# brake_light.net
KiCad netlist of a schematic drawn in EAGLE
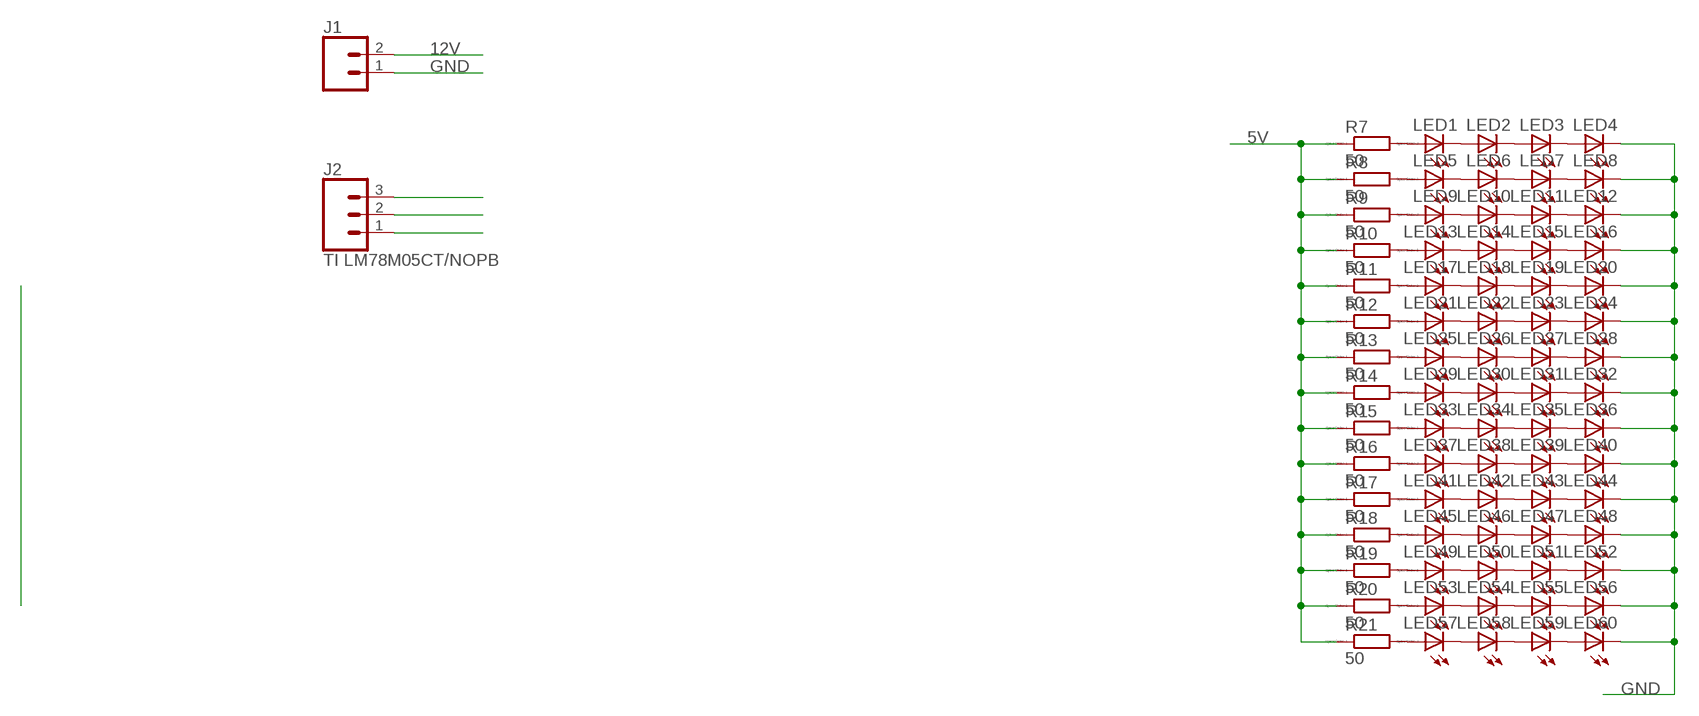
[diagram p0: schematic, sheet 1]

(export (version "E")
  (design (tool "Eeschema 10.0.6"))
  (components
    (comp (ref "J1")
      (value "CONN_02")
      (footprint "eagle-import:1X02")
      (libsource (lib "eagle-import") (part "CONN_02"))
    )
    (comp (ref "J2")
      (value "TI LM78M05CT/NOPB")
      (footprint "eagle-import:1X03")
      (libsource (lib "eagle-import") (part "CONN_03"))
    )
    (comp (ref "LED1")
      (value "LED5MM")
      (footprint "eagle-import:LED5MM")
      (libsource (lib "eagle-import") (part "LED5MM"))
    )
    (comp (ref "LED2")
      (value "LED5MM")
      (footprint "eagle-import:LED5MM")
      (libsource (lib "eagle-import") (part "LED5MM"))
    )
    (comp (ref "LED3")
      (value "LED5MM")
      (footprint "eagle-import:LED5MM")
      (libsource (lib "eagle-import") (part "LED5MM"))
    )
    (comp (ref "LED4")
      (value "LED5MM")
      (footprint "eagle-import:LED5MM")
      (libsource (lib "eagle-import") (part "LED5MM"))
    )
    (comp (ref "LED5")
      (value "LED5MM")
      (footprint "eagle-import:LED5MM")
      (libsource (lib "eagle-import") (part "LED5MM"))
    )
    (comp (ref "LED6")
      (value "LED5MM")
      (footprint "eagle-import:LED5MM")
      (libsource (lib "eagle-import") (part "LED5MM"))
    )
    (comp (ref "LED7")
      (value "LED5MM")
      (footprint "eagle-import:LED5MM")
      (libsource (lib "eagle-import") (part "LED5MM"))
    )
    (comp (ref "LED8")
      (value "LED5MM")
      (footprint "eagle-import:LED5MM")
      (libsource (lib "eagle-import") (part "LED5MM"))
    )
    (comp (ref "LED9")
      (value "LED5MM")
      (footprint "eagle-import:LED5MM")
      (libsource (lib "eagle-import") (part "LED5MM"))
    )
    (comp (ref "LED10")
      (value "LED5MM")
      (footprint "eagle-import:LED5MM")
      (libsource (lib "eagle-import") (part "LED5MM"))
    )
    (comp (ref "LED11")
      (value "LED5MM")
      (footprint "eagle-import:LED5MM")
      (libsource (lib "eagle-import") (part "LED5MM"))
    )
    (comp (ref "LED12")
      (value "LED5MM")
      (footprint "eagle-import:LED5MM")
      (libsource (lib "eagle-import") (part "LED5MM"))
    )
    (comp (ref "LED13")
      (value "LED5MM")
      (footprint "eagle-import:LED5MM")
      (libsource (lib "eagle-import") (part "LED5MM"))
    )
    (comp (ref "LED14")
      (value "LED5MM")
      (footprint "eagle-import:LED5MM")
      (libsource (lib "eagle-import") (part "LED5MM"))
    )
    (comp (ref "LED15")
      (value "LED5MM")
      (footprint "eagle-import:LED5MM")
      (libsource (lib "eagle-import") (part "LED5MM"))
    )
    (comp (ref "LED16")
      (value "LED5MM")
      (footprint "eagle-import:LED5MM")
      (libsource (lib "eagle-import") (part "LED5MM"))
    )
    (comp (ref "LED17")
      (value "LED5MM")
      (footprint "eagle-import:LED5MM")
      (libsource (lib "eagle-import") (part "LED5MM"))
    )
    (comp (ref "LED18")
      (value "LED5MM")
      (footprint "eagle-import:LED5MM")
      (libsource (lib "eagle-import") (part "LED5MM"))
    )
    (comp (ref "LED19")
      (value "LED5MM")
      (footprint "eagle-import:LED5MM")
      (libsource (lib "eagle-import") (part "LED5MM"))
    )
    (comp (ref "LED20")
      (value "LED5MM")
      (footprint "eagle-import:LED5MM")
      (libsource (lib "eagle-import") (part "LED5MM"))
    )
    (comp (ref "LED21")
      (value "LED5MM")
      (footprint "eagle-import:LED5MM")
      (libsource (lib "eagle-import") (part "LED5MM"))
    )
    (comp (ref "LED22")
      (value "LED5MM")
      (footprint "eagle-import:LED5MM")
      (libsource (lib "eagle-import") (part "LED5MM"))
    )
    (comp (ref "LED23")
      (value "LED5MM")
      (footprint "eagle-import:LED5MM")
      (libsource (lib "eagle-import") (part "LED5MM"))
    )
    (comp (ref "LED24")
      (value "LED5MM")
      (footprint "eagle-import:LED5MM")
      (libsource (lib "eagle-import") (part "LED5MM"))
    )
    (comp (ref "LED25")
      (value "LED5MM")
      (footprint "eagle-import:LED5MM")
      (libsource (lib "eagle-import") (part "LED5MM"))
    )
    (comp (ref "LED26")
      (value "LED5MM")
      (footprint "eagle-import:LED5MM")
      (libsource (lib "eagle-import") (part "LED5MM"))
    )
    (comp (ref "LED27")
      (value "LED5MM")
      (footprint "eagle-import:LED5MM")
      (libsource (lib "eagle-import") (part "LED5MM"))
    )
    (comp (ref "LED28")
      (value "LED5MM")
      (footprint "eagle-import:LED5MM")
      (libsource (lib "eagle-import") (part "LED5MM"))
    )
    (comp (ref "LED29")
      (value "LED5MM")
      (footprint "eagle-import:LED5MM")
      (libsource (lib "eagle-import") (part "LED5MM"))
    )
    (comp (ref "LED30")
      (value "LED5MM")
      (footprint "eagle-import:LED5MM")
      (libsource (lib "eagle-import") (part "LED5MM"))
    )
    (comp (ref "LED31")
      (value "LED5MM")
      (footprint "eagle-import:LED5MM")
      (libsource (lib "eagle-import") (part "LED5MM"))
    )
    (comp (ref "LED32")
      (value "LED5MM")
      (footprint "eagle-import:LED5MM")
      (libsource (lib "eagle-import") (part "LED5MM"))
    )
    (comp (ref "LED33")
      (value "LED5MM")
      (footprint "eagle-import:LED5MM")
      (libsource (lib "eagle-import") (part "LED5MM"))
    )
    (comp (ref "LED34")
      (value "LED5MM")
      (footprint "eagle-import:LED5MM")
      (libsource (lib "eagle-import") (part "LED5MM"))
    )
    (comp (ref "LED35")
      (value "LED5MM")
      (footprint "eagle-import:LED5MM")
      (libsource (lib "eagle-import") (part "LED5MM"))
    )
    (comp (ref "LED36")
      (value "LED5MM")
      (footprint "eagle-import:LED5MM")
      (libsource (lib "eagle-import") (part "LED5MM"))
    )
    (comp (ref "LED37")
      (value "LED5MM")
      (footprint "eagle-import:LED5MM")
      (libsource (lib "eagle-import") (part "LED5MM"))
    )
    (comp (ref "LED38")
      (value "LED5MM")
      (footprint "eagle-import:LED5MM")
      (libsource (lib "eagle-import") (part "LED5MM"))
    )
    (comp (ref "LED39")
      (value "LED5MM")
      (footprint "eagle-import:LED5MM")
      (libsource (lib "eagle-import") (part "LED5MM"))
    )
    (comp (ref "LED40")
      (value "LED5MM")
      (footprint "eagle-import:LED5MM")
      (libsource (lib "eagle-import") (part "LED5MM"))
    )
    (comp (ref "LED41")
      (value "LED5MM")
      (footprint "eagle-import:LED5MM")
      (libsource (lib "eagle-import") (part "LED5MM"))
    )
    (comp (ref "LED42")
      (value "LED5MM")
      (footprint "eagle-import:LED5MM")
      (libsource (lib "eagle-import") (part "LED5MM"))
    )
    (comp (ref "LED43")
      (value "LED5MM")
      (footprint "eagle-import:LED5MM")
      (libsource (lib "eagle-import") (part "LED5MM"))
    )
    (comp (ref "LED44")
      (value "LED5MM")
      (footprint "eagle-import:LED5MM")
      (libsource (lib "eagle-import") (part "LED5MM"))
    )
    (comp (ref "LED45")
      (value "LED5MM")
      (footprint "eagle-import:LED5MM")
      (libsource (lib "eagle-import") (part "LED5MM"))
    )
    (comp (ref "LED46")
      (value "LED5MM")
      (footprint "eagle-import:LED5MM")
      (libsource (lib "eagle-import") (part "LED5MM"))
    )
    (comp (ref "LED47")
      (value "LED5MM")
      (footprint "eagle-import:LED5MM")
      (libsource (lib "eagle-import") (part "LED5MM"))
    )
    (comp (ref "LED48")
      (value "LED5MM")
      (footprint "eagle-import:LED5MM")
      (libsource (lib "eagle-import") (part "LED5MM"))
    )
    (comp (ref "LED49")
      (value "LED5MM")
      (footprint "eagle-import:LED5MM")
      (libsource (lib "eagle-import") (part "LED5MM"))
    )
    (comp (ref "LED50")
      (value "LED5MM")
      (footprint "eagle-import:LED5MM")
      (libsource (lib "eagle-import") (part "LED5MM"))
    )
    (comp (ref "LED51")
      (value "LED5MM")
      (footprint "eagle-import:LED5MM")
      (libsource (lib "eagle-import") (part "LED5MM"))
    )
    (comp (ref "LED52")
      (value "LED5MM")
      (footprint "eagle-import:LED5MM")
      (libsource (lib "eagle-import") (part "LED5MM"))
    )
    (comp (ref "LED53")
      (value "LED5MM")
      (footprint "eagle-import:LED5MM")
      (libsource (lib "eagle-import") (part "LED5MM"))
    )
    (comp (ref "LED54")
      (value "LED5MM")
      (footprint "eagle-import:LED5MM")
      (libsource (lib "eagle-import") (part "LED5MM"))
    )
    (comp (ref "LED55")
      (value "LED5MM")
      (footprint "eagle-import:LED5MM")
      (libsource (lib "eagle-import") (part "LED5MM"))
    )
    (comp (ref "LED56")
      (value "LED5MM")
      (footprint "eagle-import:LED5MM")
      (libsource (lib "eagle-import") (part "LED5MM"))
    )
    (comp (ref "LED57")
      (value "LED5MM")
      (footprint "eagle-import:LED5MM")
      (libsource (lib "eagle-import") (part "LED5MM"))
    )
    (comp (ref "LED58")
      (value "LED5MM")
      (footprint "eagle-import:LED5MM")
      (libsource (lib "eagle-import") (part "LED5MM"))
    )
    (comp (ref "LED59")
      (value "LED5MM")
      (footprint "eagle-import:LED5MM")
      (libsource (lib "eagle-import") (part "LED5MM"))
    )
    (comp (ref "LED60")
      (value "LED5MM")
      (footprint "eagle-import:LED5MM")
      (libsource (lib "eagle-import") (part "LED5MM"))
    )
    (comp (ref "R7")
      (value "50")
      (footprint "eagle-import:R1206")
      (libsource (lib "eagle-import") (part "RR1206"))
    )
    (comp (ref "R8")
      (value "50")
      (footprint "eagle-import:R1206")
      (libsource (lib "eagle-import") (part "RR1206"))
    )
    (comp (ref "R9")
      (value "50")
      (footprint "eagle-import:R1206")
      (libsource (lib "eagle-import") (part "RR1206"))
    )
    (comp (ref "R10")
      (value "50")
      (footprint "eagle-import:R1206")
      (libsource (lib "eagle-import") (part "RR1206"))
    )
    (comp (ref "R11")
      (value "50")
      (footprint "eagle-import:R1206")
      (libsource (lib "eagle-import") (part "RR1206"))
    )
    (comp (ref "R12")
      (value "50")
      (footprint "eagle-import:R1206")
      (libsource (lib "eagle-import") (part "RR1206"))
    )
    (comp (ref "R13")
      (value "50")
      (footprint "eagle-import:R1206")
      (libsource (lib "eagle-import") (part "RR1206"))
    )
    (comp (ref "R14")
      (value "50")
      (footprint "eagle-import:R1206")
      (libsource (lib "eagle-import") (part "RR1206"))
    )
    (comp (ref "R15")
      (value "50")
      (footprint "eagle-import:R1206")
      (libsource (lib "eagle-import") (part "RR1206"))
    )
    (comp (ref "R16")
      (value "50")
      (footprint "eagle-import:R1206")
      (libsource (lib "eagle-import") (part "RR1206"))
    )
    (comp (ref "R17")
      (value "50")
      (footprint "eagle-import:R1206")
      (libsource (lib "eagle-import") (part "RR1206"))
    )
    (comp (ref "R18")
      (value "50")
      (footprint "eagle-import:R1206")
      (libsource (lib "eagle-import") (part "RR1206"))
    )
    (comp (ref "R19")
      (value "50")
      (footprint "eagle-import:R1206")
      (libsource (lib "eagle-import") (part "RR1206"))
    )
    (comp (ref "R20")
      (value "50")
      (footprint "eagle-import:R1206")
      (libsource (lib "eagle-import") (part "RR1206"))
    )
    (comp (ref "R21")
      (value "50")
      (footprint "eagle-import:R1206")
      (libsource (lib "eagle-import") (part "RR1206"))
    )
  )
  (nets
    (net (code "1") (name "/5V") (class "Default")
      (node (ref "J2") (pin "3") (pinfunction "3_3") (pintype "passive"))
      (node (ref "R10") (pin "1") (pinfunction "1_1") (pintype "passive"))
      (node (ref "R11") (pin "1") (pinfunction "1_1") (pintype "passive"))
      (node (ref "R12") (pin "1") (pinfunction "1_1") (pintype "passive"))
      (node (ref "R13") (pin "1") (pinfunction "1_1") (pintype "passive"))
      (node (ref "R14") (pin "1") (pinfunction "1_1") (pintype "passive"))
      (node (ref "R15") (pin "1") (pinfunction "1_1") (pintype "passive"))
      (node (ref "R16") (pin "1") (pinfunction "1_1") (pintype "passive"))
      (node (ref "R17") (pin "1") (pinfunction "1_1") (pintype "passive"))
      (node (ref "R18") (pin "1") (pinfunction "1_1") (pintype "passive"))
      (node (ref "R19") (pin "1") (pinfunction "1_1") (pintype "passive"))
      (node (ref "R20") (pin "1") (pinfunction "1_1") (pintype "passive"))
      (node (ref "R21") (pin "1") (pinfunction "1_1") (pintype "passive"))
      (node (ref "R7") (pin "1") (pinfunction "1_1") (pintype "passive"))
      (node (ref "R8") (pin "1") (pinfunction "1_1") (pintype "passive"))
      (node (ref "R9") (pin "1") (pinfunction "1_1") (pintype "passive"))
    )
    (net (code "2") (name "/12V") (class "Default")
      (node (ref "J1") (pin "2") (pinfunction "2_2") (pintype "passive"))
      (node (ref "J2") (pin "1") (pinfunction "1_1") (pintype "passive"))
    )
    (net (code "3") (name "/GND") (class "Default")
      (node (ref "J1") (pin "1") (pinfunction "1_1") (pintype "passive"))
      (node (ref "J2") (pin "2") (pinfunction "2_2") (pintype "passive"))
      (node (ref "LED12") (pin "K") (pinfunction "C_K") (pintype "passive"))
      (node (ref "LED16") (pin "K") (pinfunction "C_K") (pintype "passive"))
      (node (ref "LED20") (pin "K") (pinfunction "C_K") (pintype "passive"))
      (node (ref "LED24") (pin "K") (pinfunction "C_K") (pintype "passive"))
      (node (ref "LED28") (pin "K") (pinfunction "C_K") (pintype "passive"))
      (node (ref "LED32") (pin "K") (pinfunction "C_K") (pintype "passive"))
      (node (ref "LED36") (pin "K") (pinfunction "C_K") (pintype "passive"))
      (node (ref "LED4") (pin "K") (pinfunction "C_K") (pintype "passive"))
      (node (ref "LED40") (pin "K") (pinfunction "C_K") (pintype "passive"))
      (node (ref "LED44") (pin "K") (pinfunction "C_K") (pintype "passive"))
      (node (ref "LED48") (pin "K") (pinfunction "C_K") (pintype "passive"))
      (node (ref "LED52") (pin "K") (pinfunction "C_K") (pintype "passive"))
      (node (ref "LED56") (pin "K") (pinfunction "C_K") (pintype "passive"))
      (node (ref "LED60") (pin "K") (pinfunction "C_K") (pintype "passive"))
      (node (ref "LED8") (pin "K") (pinfunction "C_K") (pintype "passive"))
    )
    (net (code "4") (name "Net-(LED1-C)") (class "Default")
      (node (ref "LED1") (pin "K") (pinfunction "C_K") (pintype "passive"))
      (node (ref "LED2") (pin "A") (pinfunction "A_A") (pintype "passive"))
    )
    (net (code "5") (name "Net-(LED1-PadA)") (class "Default")
      (node (ref "LED1") (pin "A") (pinfunction "A_A") (pintype "passive"))
      (node (ref "R7") (pin "2") (pinfunction "2_2") (pintype "passive"))
    )
    (net (code "6") (name "Net-(LED2-C)") (class "Default")
      (node (ref "LED2") (pin "K") (pinfunction "C_K") (pintype "passive"))
      (node (ref "LED3") (pin "A") (pinfunction "A_A") (pintype "passive"))
    )
    (net (code "7") (name "Net-(LED3-C)") (class "Default")
      (node (ref "LED3") (pin "K") (pinfunction "C_K") (pintype "passive"))
      (node (ref "LED4") (pin "A") (pinfunction "A_A") (pintype "passive"))
    )
    (net (code "8") (name "Net-(LED5-C)") (class "Default")
      (node (ref "LED5") (pin "K") (pinfunction "C_K") (pintype "passive"))
      (node (ref "LED6") (pin "A") (pinfunction "A_A") (pintype "passive"))
    )
    (net (code "9") (name "Net-(LED5-PadA)") (class "Default")
      (node (ref "LED5") (pin "A") (pinfunction "A_A") (pintype "passive"))
      (node (ref "R8") (pin "2") (pinfunction "2_2") (pintype "passive"))
    )
    (net (code "10") (name "Net-(LED6-C)") (class "Default")
      (node (ref "LED6") (pin "K") (pinfunction "C_K") (pintype "passive"))
      (node (ref "LED7") (pin "A") (pinfunction "A_A") (pintype "passive"))
    )
    (net (code "11") (name "Net-(LED7-C)") (class "Default")
      (node (ref "LED7") (pin "K") (pinfunction "C_K") (pintype "passive"))
      (node (ref "LED8") (pin "A") (pinfunction "A_A") (pintype "passive"))
    )
    (net (code "12") (name "Net-(LED9-C)") (class "Default")
      (node (ref "LED10") (pin "A") (pinfunction "A_A") (pintype "passive"))
      (node (ref "LED9") (pin "K") (pinfunction "C_K") (pintype "passive"))
    )
    (net (code "13") (name "Net-(LED9-PadA)") (class "Default")
      (node (ref "LED9") (pin "A") (pinfunction "A_A") (pintype "passive"))
      (node (ref "R9") (pin "2") (pinfunction "2_2") (pintype "passive"))
    )
    (net (code "14") (name "Net-(LED10-C)") (class "Default")
      (node (ref "LED10") (pin "K") (pinfunction "C_K") (pintype "passive"))
      (node (ref "LED11") (pin "A") (pinfunction "A_A") (pintype "passive"))
    )
    (net (code "15") (name "Net-(LED11-C)") (class "Default")
      (node (ref "LED11") (pin "K") (pinfunction "C_K") (pintype "passive"))
      (node (ref "LED12") (pin "A") (pinfunction "A_A") (pintype "passive"))
    )
    (net (code "16") (name "Net-(LED13-C)") (class "Default")
      (node (ref "LED13") (pin "K") (pinfunction "C_K") (pintype "passive"))
      (node (ref "LED14") (pin "A") (pinfunction "A_A") (pintype "passive"))
    )
    (net (code "17") (name "Net-(LED13-PadA)") (class "Default")
      (node (ref "LED13") (pin "A") (pinfunction "A_A") (pintype "passive"))
      (node (ref "R10") (pin "2") (pinfunction "2_2") (pintype "passive"))
    )
    (net (code "18") (name "Net-(LED14-C)") (class "Default")
      (node (ref "LED14") (pin "K") (pinfunction "C_K") (pintype "passive"))
      (node (ref "LED15") (pin "A") (pinfunction "A_A") (pintype "passive"))
    )
    (net (code "19") (name "Net-(LED15-C)") (class "Default")
      (node (ref "LED15") (pin "K") (pinfunction "C_K") (pintype "passive"))
      (node (ref "LED16") (pin "A") (pinfunction "A_A") (pintype "passive"))
    )
    (net (code "20") (name "Net-(LED17-C)") (class "Default")
      (node (ref "LED17") (pin "K") (pinfunction "C_K") (pintype "passive"))
      (node (ref "LED18") (pin "A") (pinfunction "A_A") (pintype "passive"))
    )
    (net (code "21") (name "Net-(LED17-PadA)") (class "Default")
      (node (ref "LED17") (pin "A") (pinfunction "A_A") (pintype "passive"))
      (node (ref "R11") (pin "2") (pinfunction "2_2") (pintype "passive"))
    )
    (net (code "22") (name "Net-(LED18-C)") (class "Default")
      (node (ref "LED18") (pin "K") (pinfunction "C_K") (pintype "passive"))
      (node (ref "LED19") (pin "A") (pinfunction "A_A") (pintype "passive"))
    )
    (net (code "23") (name "Net-(LED19-C)") (class "Default")
      (node (ref "LED19") (pin "K") (pinfunction "C_K") (pintype "passive"))
      (node (ref "LED20") (pin "A") (pinfunction "A_A") (pintype "passive"))
    )
    (net (code "24") (name "Net-(LED21-C)") (class "Default")
      (node (ref "LED21") (pin "K") (pinfunction "C_K") (pintype "passive"))
      (node (ref "LED22") (pin "A") (pinfunction "A_A") (pintype "passive"))
    )
    (net (code "25") (name "Net-(LED21-PadA)") (class "Default")
      (node (ref "LED21") (pin "A") (pinfunction "A_A") (pintype "passive"))
      (node (ref "R12") (pin "2") (pinfunction "2_2") (pintype "passive"))
    )
    (net (code "26") (name "Net-(LED22-C)") (class "Default")
      (node (ref "LED22") (pin "K") (pinfunction "C_K") (pintype "passive"))
      (node (ref "LED23") (pin "A") (pinfunction "A_A") (pintype "passive"))
    )
    (net (code "27") (name "Net-(LED23-C)") (class "Default")
      (node (ref "LED23") (pin "K") (pinfunction "C_K") (pintype "passive"))
      (node (ref "LED24") (pin "A") (pinfunction "A_A") (pintype "passive"))
    )
    (net (code "28") (name "Net-(LED25-C)") (class "Default")
      (node (ref "LED25") (pin "K") (pinfunction "C_K") (pintype "passive"))
      (node (ref "LED26") (pin "A") (pinfunction "A_A") (pintype "passive"))
    )
    (net (code "29") (name "Net-(LED25-PadA)") (class "Default")
      (node (ref "LED25") (pin "A") (pinfunction "A_A") (pintype "passive"))
      (node (ref "R13") (pin "2") (pinfunction "2_2") (pintype "passive"))
    )
    (net (code "30") (name "Net-(LED26-C)") (class "Default")
      (node (ref "LED26") (pin "K") (pinfunction "C_K") (pintype "passive"))
      (node (ref "LED27") (pin "A") (pinfunction "A_A") (pintype "passive"))
    )
    (net (code "31") (name "Net-(LED27-C)") (class "Default")
      (node (ref "LED27") (pin "K") (pinfunction "C_K") (pintype "passive"))
      (node (ref "LED28") (pin "A") (pinfunction "A_A") (pintype "passive"))
    )
    (net (code "32") (name "Net-(LED29-C)") (class "Default")
      (node (ref "LED29") (pin "K") (pinfunction "C_K") (pintype "passive"))
      (node (ref "LED30") (pin "A") (pinfunction "A_A") (pintype "passive"))
    )
    (net (code "33") (name "Net-(LED29-PadA)") (class "Default")
      (node (ref "LED29") (pin "A") (pinfunction "A_A") (pintype "passive"))
      (node (ref "R14") (pin "2") (pinfunction "2_2") (pintype "passive"))
    )
    (net (code "34") (name "Net-(LED30-C)") (class "Default")
      (node (ref "LED30") (pin "K") (pinfunction "C_K") (pintype "passive"))
      (node (ref "LED31") (pin "A") (pinfunction "A_A") (pintype "passive"))
    )
    (net (code "35") (name "Net-(LED31-C)") (class "Default")
      (node (ref "LED31") (pin "K") (pinfunction "C_K") (pintype "passive"))
      (node (ref "LED32") (pin "A") (pinfunction "A_A") (pintype "passive"))
    )
    (net (code "36") (name "Net-(LED33-C)") (class "Default")
      (node (ref "LED33") (pin "K") (pinfunction "C_K") (pintype "passive"))
      (node (ref "LED34") (pin "A") (pinfunction "A_A") (pintype "passive"))
    )
    (net (code "37") (name "Net-(LED33-PadA)") (class "Default")
      (node (ref "LED33") (pin "A") (pinfunction "A_A") (pintype "passive"))
      (node (ref "R15") (pin "2") (pinfunction "2_2") (pintype "passive"))
    )
    (net (code "38") (name "Net-(LED34-C)") (class "Default")
      (node (ref "LED34") (pin "K") (pinfunction "C_K") (pintype "passive"))
      (node (ref "LED35") (pin "A") (pinfunction "A_A") (pintype "passive"))
    )
    (net (code "39") (name "Net-(LED35-C)") (class "Default")
      (node (ref "LED35") (pin "K") (pinfunction "C_K") (pintype "passive"))
      (node (ref "LED36") (pin "A") (pinfunction "A_A") (pintype "passive"))
    )
    (net (code "40") (name "Net-(LED37-C)") (class "Default")
      (node (ref "LED37") (pin "K") (pinfunction "C_K") (pintype "passive"))
      (node (ref "LED38") (pin "A") (pinfunction "A_A") (pintype "passive"))
    )
    (net (code "41") (name "Net-(LED37-PadA)") (class "Default")
      (node (ref "LED37") (pin "A") (pinfunction "A_A") (pintype "passive"))
      (node (ref "R16") (pin "2") (pinfunction "2_2") (pintype "passive"))
    )
    (net (code "42") (name "Net-(LED38-C)") (class "Default")
      (node (ref "LED38") (pin "K") (pinfunction "C_K") (pintype "passive"))
      (node (ref "LED39") (pin "A") (pinfunction "A_A") (pintype "passive"))
    )
    (net (code "43") (name "Net-(LED39-C)") (class "Default")
      (node (ref "LED39") (pin "K") (pinfunction "C_K") (pintype "passive"))
      (node (ref "LED40") (pin "A") (pinfunction "A_A") (pintype "passive"))
    )
    (net (code "44") (name "Net-(LED41-C)") (class "Default")
      (node (ref "LED41") (pin "K") (pinfunction "C_K") (pintype "passive"))
      (node (ref "LED42") (pin "A") (pinfunction "A_A") (pintype "passive"))
    )
    (net (code "45") (name "Net-(LED41-PadA)") (class "Default")
      (node (ref "LED41") (pin "A") (pinfunction "A_A") (pintype "passive"))
      (node (ref "R17") (pin "2") (pinfunction "2_2") (pintype "passive"))
    )
    (net (code "46") (name "Net-(LED42-C)") (class "Default")
      (node (ref "LED42") (pin "K") (pinfunction "C_K") (pintype "passive"))
      (node (ref "LED43") (pin "A") (pinfunction "A_A") (pintype "passive"))
    )
    (net (code "47") (name "Net-(LED43-C)") (class "Default")
      (node (ref "LED43") (pin "K") (pinfunction "C_K") (pintype "passive"))
      (node (ref "LED44") (pin "A") (pinfunction "A_A") (pintype "passive"))
    )
    (net (code "48") (name "Net-(LED45-C)") (class "Default")
      (node (ref "LED45") (pin "K") (pinfunction "C_K") (pintype "passive"))
      (node (ref "LED46") (pin "A") (pinfunction "A_A") (pintype "passive"))
    )
    (net (code "49") (name "Net-(LED45-PadA)") (class "Default")
      (node (ref "LED45") (pin "A") (pinfunction "A_A") (pintype "passive"))
      (node (ref "R18") (pin "2") (pinfunction "2_2") (pintype "passive"))
    )
    (net (code "50") (name "Net-(LED46-C)") (class "Default")
      (node (ref "LED46") (pin "K") (pinfunction "C_K") (pintype "passive"))
      (node (ref "LED47") (pin "A") (pinfunction "A_A") (pintype "passive"))
    )
    (net (code "51") (name "Net-(LED47-C)") (class "Default")
      (node (ref "LED47") (pin "K") (pinfunction "C_K") (pintype "passive"))
      (node (ref "LED48") (pin "A") (pinfunction "A_A") (pintype "passive"))
    )
    (net (code "52") (name "Net-(LED49-C)") (class "Default")
      (node (ref "LED49") (pin "K") (pinfunction "C_K") (pintype "passive"))
      (node (ref "LED50") (pin "A") (pinfunction "A_A") (pintype "passive"))
    )
    (net (code "53") (name "Net-(LED49-PadA)") (class "Default")
      (node (ref "LED49") (pin "A") (pinfunction "A_A") (pintype "passive"))
      (node (ref "R19") (pin "2") (pinfunction "2_2") (pintype "passive"))
    )
    (net (code "54") (name "Net-(LED50-C)") (class "Default")
      (node (ref "LED50") (pin "K") (pinfunction "C_K") (pintype "passive"))
      (node (ref "LED51") (pin "A") (pinfunction "A_A") (pintype "passive"))
    )
    (net (code "55") (name "Net-(LED51-C)") (class "Default")
      (node (ref "LED51") (pin "K") (pinfunction "C_K") (pintype "passive"))
      (node (ref "LED52") (pin "A") (pinfunction "A_A") (pintype "passive"))
    )
    (net (code "56") (name "Net-(LED53-C)") (class "Default")
      (node (ref "LED53") (pin "K") (pinfunction "C_K") (pintype "passive"))
      (node (ref "LED54") (pin "A") (pinfunction "A_A") (pintype "passive"))
    )
    (net (code "57") (name "Net-(LED53-PadA)") (class "Default")
      (node (ref "LED53") (pin "A") (pinfunction "A_A") (pintype "passive"))
      (node (ref "R20") (pin "2") (pinfunction "2_2") (pintype "passive"))
    )
    (net (code "58") (name "Net-(LED54-C)") (class "Default")
      (node (ref "LED54") (pin "K") (pinfunction "C_K") (pintype "passive"))
      (node (ref "LED55") (pin "A") (pinfunction "A_A") (pintype "passive"))
    )
    (net (code "59") (name "Net-(LED55-C)") (class "Default")
      (node (ref "LED55") (pin "K") (pinfunction "C_K") (pintype "passive"))
      (node (ref "LED56") (pin "A") (pinfunction "A_A") (pintype "passive"))
    )
    (net (code "60") (name "Net-(LED57-C)") (class "Default")
      (node (ref "LED57") (pin "K") (pinfunction "C_K") (pintype "passive"))
      (node (ref "LED58") (pin "A") (pinfunction "A_A") (pintype "passive"))
    )
    (net (code "61") (name "Net-(LED57-PadA)") (class "Default")
      (node (ref "LED57") (pin "A") (pinfunction "A_A") (pintype "passive"))
      (node (ref "R21") (pin "2") (pinfunction "2_2") (pintype "passive"))
    )
    (net (code "62") (name "Net-(LED58-C)") (class "Default")
      (node (ref "LED58") (pin "K") (pinfunction "C_K") (pintype "passive"))
      (node (ref "LED59") (pin "A") (pinfunction "A_A") (pintype "passive"))
    )
    (net (code "63") (name "Net-(LED59-C)") (class "Default")
      (node (ref "LED59") (pin "K") (pinfunction "C_K") (pintype "passive"))
      (node (ref "LED60") (pin "A") (pinfunction "A_A") (pintype "passive"))
    )
  )
)
